# atividade_02.net
KiCad netlist of a schematic drawn in EAGLE
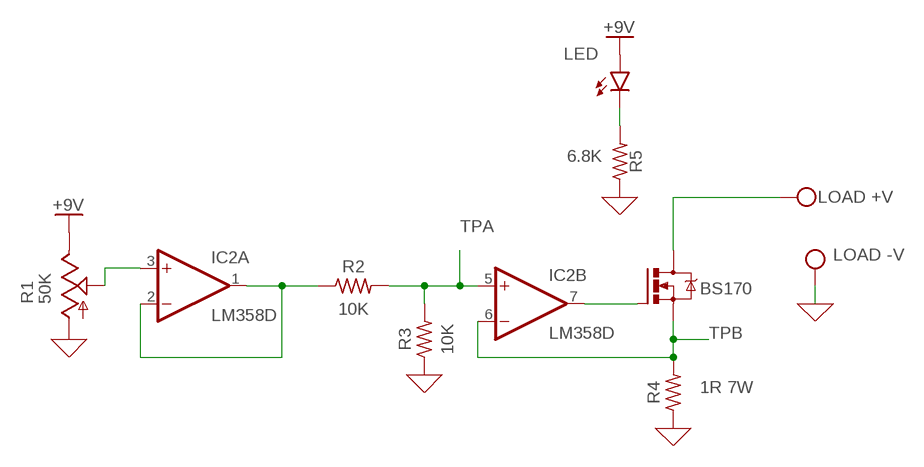
[diagram p0: schematic, sheet 1]

(export (version "E")
  (design (tool "Eeschema 10.0.6"))
  (components
    (comp (ref "IC2")
      (value "LM358D")
      (footprint "eagle-import:SO08")
      (libsource (lib "eagle-import") (part "LM358D"))
    )
    (comp (ref "LED")
      (value "LAP4-BOTTOM")
      (footprint "eagle-import:P47F-BOTTOM")
      (libsource (lib "eagle-import") (part "P4-BOTTOMLA"))
    )
    (comp (ref "Q1")
      (value "BS170")
      (footprint "eagle-import:TO92")
      (fields (field (name "MANUFACTURER") "ON Semiconductor"))
      (libsource (lib "eagle-import") (part "NMOSFET_-TO92BS170"))
    )
    (comp (ref "R1")
      (value "50K")
      (footprint "eagle-import:B25P")
      (libsource (lib "eagle-import") (part "TRIM_US-B25P"))
    )
    (comp (ref "R2")
      (value "10K")
      (footprint "eagle-import:RESAD724W46L381D178B")
      (libsource (lib "eagle-import") (part "R-USAXIAL-7.2MM-PITCH_"))
    )
    (comp (ref "R3")
      (value "10K")
      (footprint "eagle-import:RESAD724W46L381D178B")
      (libsource (lib "eagle-import") (part "R-USAXIAL-7.2MM-PITCH_"))
    )
    (comp (ref "R4")
      (value "1R 7W")
      (footprint "eagle-import:RESAD724W46L381D178B")
      (libsource (lib "eagle-import") (part "R-USAXIAL-7.2MM-PITCH_"))
    )
    (comp (ref "R5")
      (value "6.8K")
      (footprint "eagle-import:RESAD724W46L381D178B")
      (libsource (lib "eagle-import") (part "R-USAXIAL-7.2MM-PITCH_"))
    )
  )
  (nets
    (net (code "1") (name "+9V") (class "Default")
      (node (ref "LED") (pin "A") (pinfunction "A_A") (pintype "passive"))
      (node (ref "R1") (pin "E") (pinfunction "E_E") (pintype "passive"))
    )
    (net (code "2") (name "/TPA") (class "Default")
      (node (ref "IC2") (pin "5") (pinfunction "+IN_5") (pintype "input"))
      (node (ref "R2") (pin "2") (pinfunction "2_2") (pintype "passive"))
      (node (ref "R3") (pin "2") (pinfunction "2_2") (pintype "passive"))
    )
    (net (code "3") (name "/TPB") (class "Default")
      (node (ref "IC2") (pin "6") (pinfunction "-IN_6") (pintype "input"))
      (node (ref "Q1") (pin "3") (pinfunction "S_3") (pintype "passive"))
      (node (ref "R4") (pin "2") (pinfunction "2_2") (pintype "passive"))
    )
    (net (code "4") (name "GND") (class "Default")
      (node (ref "R1") (pin "A") (pinfunction "A_A") (pintype "passive"))
      (node (ref "R3") (pin "1") (pinfunction "1_1") (pintype "passive"))
      (node (ref "R4") (pin "1") (pinfunction "1_1") (pintype "passive"))
      (node (ref "R5") (pin "1") (pinfunction "1_1") (pintype "passive"))
    )
    (net (code "5") (name "LOAD +V") (class "Default")
      (node (ref "Q1") (pin "1") (pinfunction "D_1") (pintype "passive"))
    )
    (net (code "6") (name "Net-(IC2A-+IN)") (class "Default")
      (node (ref "IC2") (pin "3") (pinfunction "+IN_3") (pintype "input"))
      (node (ref "R1") (pin "S") (pinfunction "S_S") (pintype "passive"))
    )
    (net (code "7") (name "Net-(IC2A--IN)") (class "Default")
      (node (ref "IC2") (pin "1") (pinfunction "OUT_1") (pintype "output"))
      (node (ref "IC2") (pin "2") (pinfunction "-IN_2") (pintype "input"))
      (node (ref "R2") (pin "1") (pinfunction "1_1") (pintype "passive"))
    )
    (net (code "8") (name "Net-(IC2B-OUT)") (class "Default")
      (node (ref "IC2") (pin "7") (pinfunction "OUT_7") (pintype "output"))
      (node (ref "Q1") (pin "2") (pinfunction "G_2") (pintype "passive"))
    )
    (net (code "9") (name "Net-(LED-PadC)") (class "Default")
      (node (ref "LED") (pin "C") (pinfunction "C_C") (pintype "passive"))
      (node (ref "R5") (pin "2") (pinfunction "2_2") (pintype "passive"))
    )
  )
)
